# base.net
KiCad netlist of a schematic drawn in EAGLE
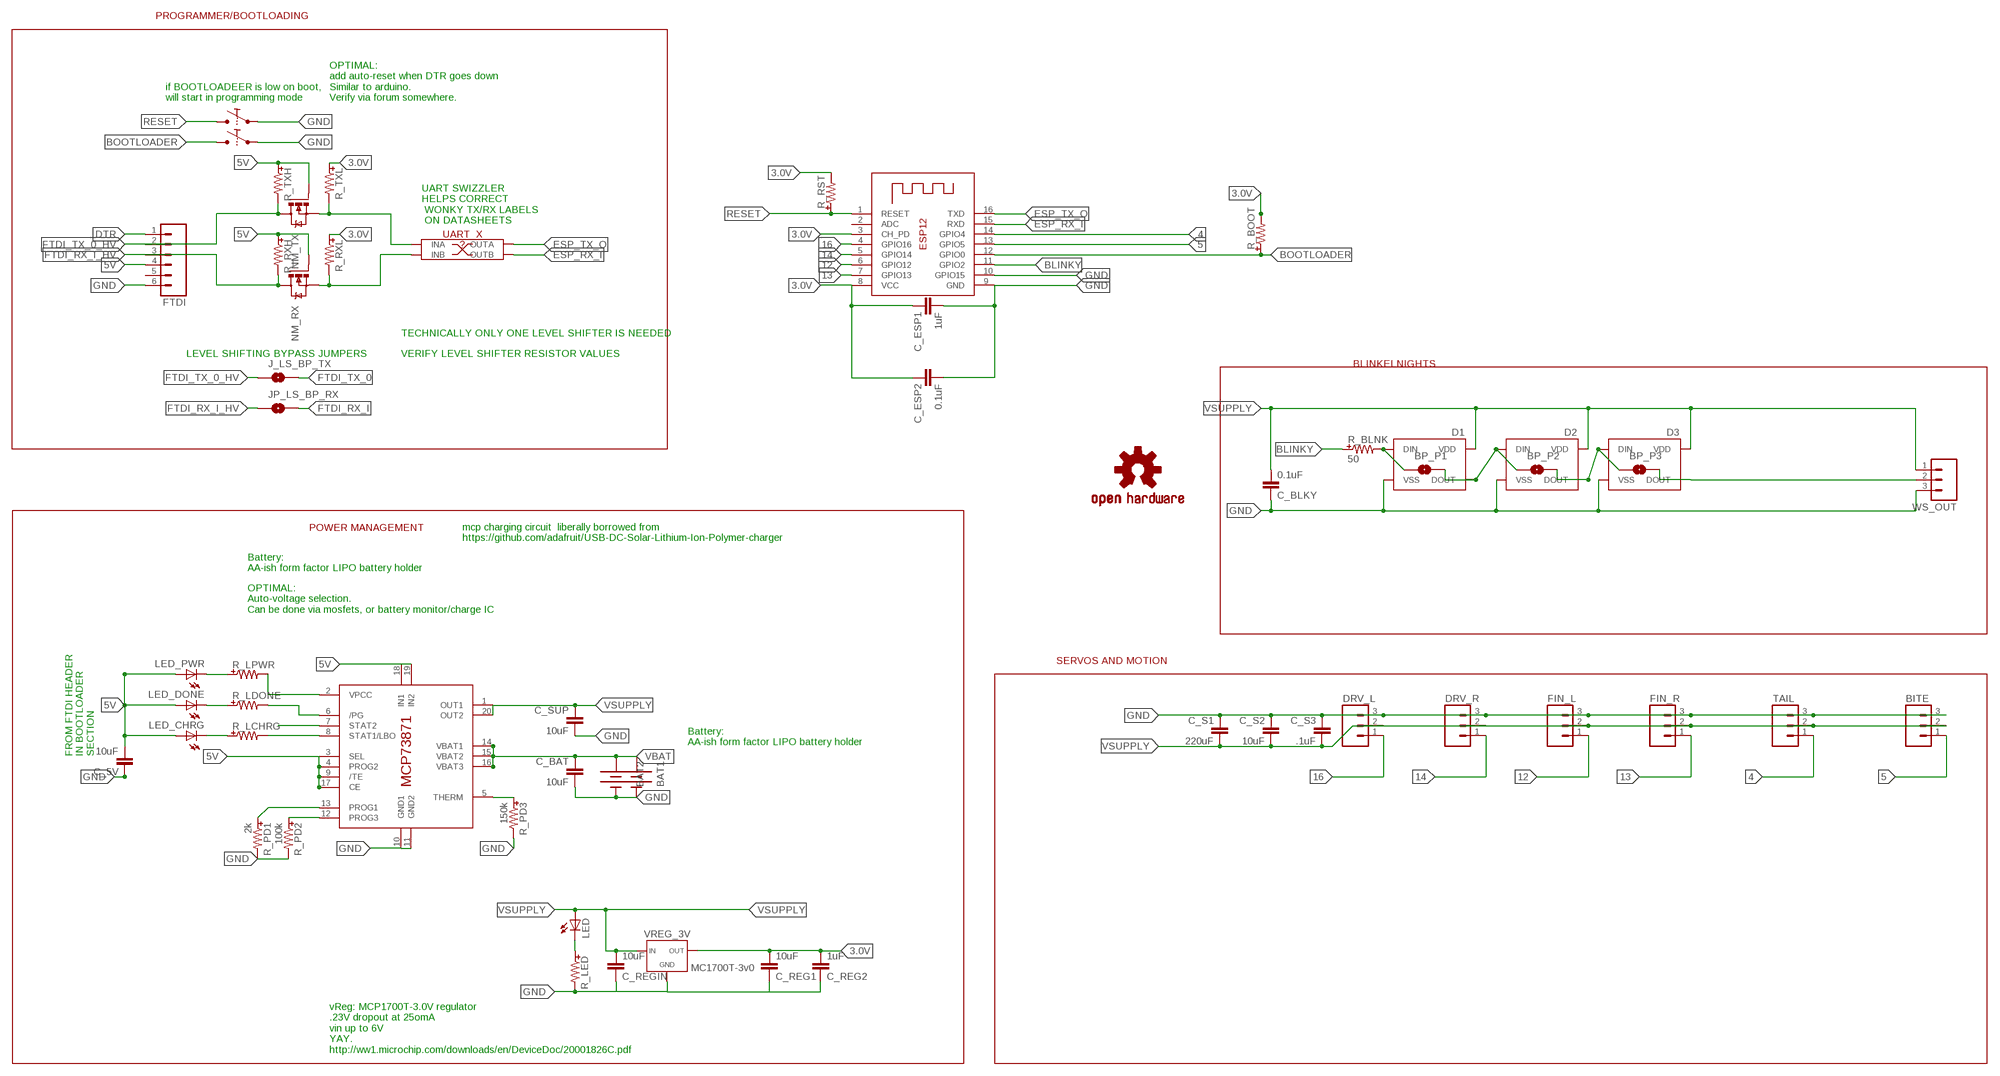
[diagram p0: schematic, sheet 1]

(export (version "E")
  (design (tool "Eeschema 10.0.6"))
  (components
    (comp (ref "BAT1")
      (value "BATTERY18650")
      (footprint "eagle-import:BATTERY_18650-HOLDER")
      (libsource (lib "eagle-import") (part "BATTERY18650"))
    )
    (comp (ref "BAT2")
      (value "BATTERYAA")
      (footprint "eagle-import:BATTERY-AA")
      (libsource (lib "eagle-import") (part "BATTERYAA"))
    )
    (comp (ref "BITE")
      (value "M03LOCK")
      (footprint "eagle-import:1X03_LOCK")
      (libsource (lib "eagle-import") (part "M03LOCK"))
    )
    (comp (ref "BP_P1")
      (value "JUMPER-PAD-2-NOYES_SILK")
      (footprint "eagle-import:PAD-JUMPER-2-NO_YES_SILK")
      (libsource (lib "eagle-import") (part "JUMPER-PAD-2-NOYES_SILK"))
    )
    (comp (ref "BP_P2")
      (value "JUMPER-PAD-2-NOYES_SILK")
      (footprint "eagle-import:PAD-JUMPER-2-NO_YES_SILK")
      (libsource (lib "eagle-import") (part "JUMPER-PAD-2-NOYES_SILK"))
    )
    (comp (ref "BP_P3")
      (value "JUMPER-PAD-2-NOYES_SILK")
      (footprint "eagle-import:PAD-JUMPER-2-NO_YES_SILK")
      (libsource (lib "eagle-import") (part "JUMPER-PAD-2-NOYES_SILK"))
    )
    (comp (ref "BTN_PROG")
      (value "BUTTONPJRC")
      (footprint "eagle-import:BUTTON-PJRC")
      (libsource (lib "eagle-import") (part "BUTTONPJRC"))
    )
    (comp (ref "BTN_RST")
      (value "BUTTONPJRC")
      (footprint "eagle-import:BUTTON-PJRC")
      (libsource (lib "eagle-import") (part "BUTTONPJRC"))
    )
    (comp (ref "C_5V")
      (value "10uF")
      (footprint "eagle-import:0402-0603-0805-UNIVERSAL")
      (libsource (lib "eagle-import") (part "CAPUNIVERSAL"))
    )
    (comp (ref "C_BAT")
      (value "10uF")
      (footprint "eagle-import:0402-0603-0805-UNIVERSAL")
      (libsource (lib "eagle-import") (part "CAPUNIVERSAL"))
    )
    (comp (ref "C_BLKY")
      (value "0.1uF")
      (footprint "eagle-import:0402-0603-0805-UNIVERSAL")
      (libsource (lib "eagle-import") (part "CAPUNIVERSAL"))
    )
    (comp (ref "C_ESP1")
      (value "1uF")
      (footprint "eagle-import:0402-0603-0805-UNIVERSAL")
      (libsource (lib "eagle-import") (part "CAPUNIVERSAL"))
    )
    (comp (ref "C_ESP2")
      (value "0.1uF")
      (footprint "eagle-import:0402-0603-0805-UNIVERSAL")
      (libsource (lib "eagle-import") (part "CAPUNIVERSAL"))
    )
    (comp (ref "C_REG1")
      (value "10uF")
      (footprint "eagle-import:0402-0603-0805-UNIVERSAL")
      (libsource (lib "eagle-import") (part "CAPUNIVERSAL"))
    )
    (comp (ref "C_REG2")
      (value "1uF")
      (footprint "eagle-import:0402-0603-0805-UNIVERSAL")
      (libsource (lib "eagle-import") (part "CAPUNIVERSAL"))
    )
    (comp (ref "C_REGIN")
      (value "10uF")
      (footprint "eagle-import:0402-0603-0805-UNIVERSAL")
      (libsource (lib "eagle-import") (part "CAPUNIVERSAL"))
    )
    (comp (ref "C_S1")
      (value "220uF")
      (footprint "eagle-import:0402-0603-0805-UNIVERSAL")
      (libsource (lib "eagle-import") (part "CAPUNIVERSAL"))
    )
    (comp (ref "C_S2")
      (value "10uF")
      (footprint "eagle-import:0402-0603-0805-UNIVERSAL")
      (libsource (lib "eagle-import") (part "CAPUNIVERSAL"))
    )
    (comp (ref "C_S3")
      (value ".1uF")
      (footprint "eagle-import:0402-0603-0805-UNIVERSAL")
      (libsource (lib "eagle-import") (part "CAPUNIVERSAL"))
    )
    (comp (ref "C_SUP")
      (value "10uF")
      (footprint "eagle-import:0402-0603-0805-UNIVERSAL")
      (libsource (lib "eagle-import") (part "CAPUNIVERSAL"))
    )
    (comp (ref "D1")
      (value "WS2812B")
      (footprint "eagle-import:WS2812B")
      (libsource (lib "eagle-import") (part "WS2812B"))
    )
    (comp (ref "D2")
      (value "WS2812B")
      (footprint "eagle-import:WS2812B")
      (libsource (lib "eagle-import") (part "WS2812B"))
    )
    (comp (ref "D3")
      (value "WS2812B")
      (footprint "eagle-import:WS2812B")
      (libsource (lib "eagle-import") (part "WS2812B"))
    )
    (comp (ref "DRV_L")
      (value "M03LOCK")
      (footprint "eagle-import:1X03_LOCK")
      (libsource (lib "eagle-import") (part "M03LOCK"))
    )
    (comp (ref "DRV_R")
      (value "M03LOCK")
      (footprint "eagle-import:1X03_LOCK")
      (libsource (lib "eagle-import") (part "M03LOCK"))
    )
    (comp (ref "FIN_L")
      (value "M03LOCK")
      (footprint "eagle-import:1X03_LOCK")
      (libsource (lib "eagle-import") (part "M03LOCK"))
    )
    (comp (ref "FIN_R")
      (value "M03LOCK")
      (footprint "eagle-import:1X03_LOCK")
      (libsource (lib "eagle-import") (part "M03LOCK"))
    )
    (comp (ref "FTDI")
      (value "M06LOCK")
      (footprint "eagle-import:1X06_LOCK")
      (libsource (lib "eagle-import") (part "M06LOCK"))
    )
    (comp (ref "IC_LIPO")
      (value "MCP73871")
      (footprint "eagle-import:QFN20")
      (libsource (lib "eagle-import") (part "MCP73871"))
    )
    (comp (ref "JP_LS_BP_RX")
      (value "JUMPER-PAD-2-NOYES_SILK")
      (footprint "eagle-import:PAD-JUMPER-2-NO_YES_SILK")
      (libsource (lib "eagle-import") (part "JUMPER-PAD-2-NOYES_SILK"))
    )
    (comp (ref "J_LS_BP_TX")
      (value "JUMPER-PAD-2-NOYES_SILK")
      (footprint "eagle-import:PAD-JUMPER-2-NO_YES_SILK")
      (libsource (lib "eagle-import") (part "JUMPER-PAD-2-NOYES_SILK"))
    )
    (comp (ref "LED")
      (value "LEDUNIVERSAL")
      (footprint "eagle-import:0402-0603-0805-UNIVERSAL")
      (libsource (lib "eagle-import") (part "LEDUNIVERSAL"))
    )
    (comp (ref "LED_CHRG")
      (value "LEDUNIVERSAL")
      (footprint "eagle-import:0402-0603-0805-UNIVERSAL")
      (libsource (lib "eagle-import") (part "LEDUNIVERSAL"))
    )
    (comp (ref "LED_DONE")
      (value "LEDUNIVERSAL")
      (footprint "eagle-import:0402-0603-0805-UNIVERSAL")
      (libsource (lib "eagle-import") (part "LEDUNIVERSAL"))
    )
    (comp (ref "LED_PWR")
      (value "LEDUNIVERSAL")
      (footprint "eagle-import:0402-0603-0805-UNIVERSAL")
      (libsource (lib "eagle-import") (part "LEDUNIVERSAL"))
    )
    (comp (ref "LOGO1")
      (value "OSHW-LOGOS")
      (footprint "eagle-import:OSHW-LOGO-S")
      (libsource (lib "eagle-import") (part "OSHW-LOGOS"))
    )
    (comp (ref "NM_RX")
      (value "MOSFET-NCHANNELSMD")
      (footprint "eagle-import:SOT23-3")
      (libsource (lib "eagle-import") (part "MOSFET-NCHANNELSMD"))
    )
    (comp (ref "NM_TX")
      (value "MOSFET-NCHANNELSMD")
      (footprint "eagle-import:SOT23-3")
      (libsource (lib "eagle-import") (part "MOSFET-NCHANNELSMD"))
    )
    (comp (ref "R_BLNK")
      (value "50")
      (footprint "eagle-import:0402-0603-0805-UNIVERSAL")
      (libsource (lib "eagle-import") (part "RESISTORUNIVERSAL"))
    )
    (comp (ref "R_BOOT")
      (value "RESISTORUNIVERSAL")
      (footprint "eagle-import:0402-0603-0805-UNIVERSAL")
      (libsource (lib "eagle-import") (part "RESISTORUNIVERSAL"))
    )
    (comp (ref "R_LCHRG")
      (value "RESISTORUNIVERSAL")
      (footprint "eagle-import:0402-0603-0805-UNIVERSAL")
      (libsource (lib "eagle-import") (part "RESISTORUNIVERSAL"))
    )
    (comp (ref "R_LDONE")
      (value "RESISTORUNIVERSAL")
      (footprint "eagle-import:0402-0603-0805-UNIVERSAL")
      (libsource (lib "eagle-import") (part "RESISTORUNIVERSAL"))
    )
    (comp (ref "R_LED")
      (value "RESISTORUNIVERSAL")
      (footprint "eagle-import:0402-0603-0805-UNIVERSAL")
      (libsource (lib "eagle-import") (part "RESISTORUNIVERSAL"))
    )
    (comp (ref "R_LPWR")
      (value "RESISTORUNIVERSAL")
      (footprint "eagle-import:0402-0603-0805-UNIVERSAL")
      (libsource (lib "eagle-import") (part "RESISTORUNIVERSAL"))
    )
    (comp (ref "R_PD1")
      (value "2k")
      (footprint "eagle-import:0402-0603-0805-UNIVERSAL")
      (libsource (lib "eagle-import") (part "RESISTORUNIVERSAL"))
    )
    (comp (ref "R_PD2")
      (value "100k")
      (footprint "eagle-import:0402-0603-0805-UNIVERSAL")
      (libsource (lib "eagle-import") (part "RESISTORUNIVERSAL"))
    )
    (comp (ref "R_PD3")
      (value "150k")
      (footprint "eagle-import:0402-0603-0805-UNIVERSAL")
      (libsource (lib "eagle-import") (part "RESISTORUNIVERSAL"))
    )
    (comp (ref "R_RST")
      (value "RESISTORUNIVERSAL")
      (footprint "eagle-import:0402-0603-0805-UNIVERSAL")
      (libsource (lib "eagle-import") (part "RESISTORUNIVERSAL"))
    )
    (comp (ref "R_RXH")
      (value "RESISTORUNIVERSAL")
      (footprint "eagle-import:0402-0603-0805-UNIVERSAL")
      (libsource (lib "eagle-import") (part "RESISTORUNIVERSAL"))
    )
    (comp (ref "R_RXL")
      (value "RESISTORUNIVERSAL")
      (footprint "eagle-import:0402-0603-0805-UNIVERSAL")
      (libsource (lib "eagle-import") (part "RESISTORUNIVERSAL"))
    )
    (comp (ref "R_TXH")
      (value "RESISTORUNIVERSAL")
      (footprint "eagle-import:0402-0603-0805-UNIVERSAL")
      (libsource (lib "eagle-import") (part "RESISTORUNIVERSAL"))
    )
    (comp (ref "R_TXL")
      (value "RESISTORUNIVERSAL")
      (footprint "eagle-import:0402-0603-0805-UNIVERSAL")
      (libsource (lib "eagle-import") (part "RESISTORUNIVERSAL"))
    )
    (comp (ref "TAIL")
      (value "M03LOCK")
      (footprint "eagle-import:1X03_LOCK")
      (libsource (lib "eagle-import") (part "M03LOCK"))
    )
    (comp (ref "UART_X")
      (value "UART_SWITCHER0603")
      (footprint "eagle-import:UART_SWITCHER_0603")
      (libsource (lib "eagle-import") (part "UART_SWITCHER0603"))
    )
    (comp (ref "VREG_3V")
      (value "MC1700T-3v0")
      (footprint "eagle-import:SOT23")
      (libsource (lib "eagle-import") (part "VOLTAGE-REGULATORMCP1703"))
    )
    (comp (ref "WS_OUT")
      (value "M03LOCK")
      (footprint "eagle-import:1X03_LOCK")
      (libsource (lib "eagle-import") (part "M03LOCK"))
    )
    (comp (ref "X1")
      (value "ESP-12")
      (footprint "eagle-import:ESP-12")
      (libsource (lib "eagle-import") (part "ESP-12"))
    )
  )
  (nets
    (net (code "1") (name "3.0V") (class "Default")
      (node (ref "C_ESP1") (pin "-") (pinfunction "1_-") (pintype "passive"))
      (node (ref "C_ESP2") (pin "-") (pinfunction "1_-") (pintype "passive"))
      (node (ref "C_REG1") (pin "+") (pinfunction "2_+") (pintype "passive"))
      (node (ref "C_REG2") (pin "+") (pinfunction "2_+") (pintype "passive"))
      (node (ref "R_BOOT") (pin "-") (pinfunction "2_-") (pintype "passive"))
      (node (ref "R_RST") (pin "-") (pinfunction "2_-") (pintype "passive"))
      (node (ref "R_RXL") (pin "+") (pinfunction "1_+") (pintype "passive"))
      (node (ref "R_TXL") (pin "+") (pinfunction "1_+") (pintype "passive"))
      (node (ref "VREG_3V") (pin "2") (pinfunction "OUT_2") (pintype "input"))
      (node (ref "X1") (pin "3") (pinfunction "CH_PD_3") (pintype "input"))
      (node (ref "X1") (pin "8") (pinfunction "VCC_8") (pintype "power_in"))
    )
    (net (code "2") (name "4") (class "Default")
      (node (ref "TAIL") (pin "1") (pinfunction "1_1") (pintype "passive"))
      (node (ref "X1") (pin "14") (pinfunction "GPIO4_14") (pintype "bidirectional"))
    )
    (net (code "3") (name "5") (class "Default")
      (node (ref "BITE") (pin "1") (pinfunction "1_1") (pintype "passive"))
      (node (ref "X1") (pin "13") (pinfunction "GPIO5_13") (pintype "bidirectional"))
    )
    (net (code "4") (name "5V") (class "Default")
      (node (ref "C_5V") (pin "+") (pinfunction "2_+") (pintype "passive"))
      (node (ref "FTDI") (pin "4") (pinfunction "4_4") (pintype "passive"))
      (node (ref "IC_LIPO") (pin "17") (pinfunction "CE_17") (pintype "input"))
      (node (ref "IC_LIPO") (pin "18") (pinfunction "IN1_18") (pintype "input"))
      (node (ref "IC_LIPO") (pin "19") (pinfunction "IN2_19") (pintype "input"))
      (node (ref "IC_LIPO") (pin "3") (pinfunction "SEL_3") (pintype "input"))
      (node (ref "IC_LIPO") (pin "4") (pinfunction "PROG2_4") (pintype "input"))
      (node (ref "IC_LIPO") (pin "9") (pinfunction "/TE_9") (pintype "input"))
      (node (ref "LED_CHRG") (pin "+") (pinfunction "A_+") (pintype "passive"))
      (node (ref "LED_DONE") (pin "+") (pinfunction "A_+") (pintype "passive"))
      (node (ref "LED_PWR") (pin "+") (pinfunction "A_+") (pintype "passive"))
      (node (ref "NM_RX") (pin "1") (pinfunction "G_1") (pintype "passive"))
      (node (ref "NM_TX") (pin "1") (pinfunction "G_1") (pintype "passive"))
      (node (ref "R_RXH") (pin "+") (pinfunction "1_+") (pintype "passive"))
      (node (ref "R_TXH") (pin "+") (pinfunction "1_+") (pintype "passive"))
    )
    (net (code "5") (name "12") (class "Default")
      (node (ref "FIN_L") (pin "1") (pinfunction "1_1") (pintype "passive"))
      (node (ref "X1") (pin "6") (pinfunction "GPIO12_6") (pintype "bidirectional"))
    )
    (net (code "6") (name "13") (class "Default")
      (node (ref "FIN_R") (pin "1") (pinfunction "1_1") (pintype "passive"))
      (node (ref "X1") (pin "7") (pinfunction "GPIO13_7") (pintype "bidirectional"))
    )
    (net (code "7") (name "14") (class "Default")
      (node (ref "DRV_R") (pin "1") (pinfunction "1_1") (pintype "passive"))
      (node (ref "X1") (pin "5") (pinfunction "GPIO14_5") (pintype "bidirectional"))
    )
    (net (code "8") (name "16") (class "Default")
      (node (ref "DRV_L") (pin "1") (pinfunction "1_1") (pintype "passive"))
      (node (ref "X1") (pin "4") (pinfunction "GPIO16_4") (pintype "bidirectional"))
    )
    (net (code "9") (name "BLINKY") (class "Default")
      (node (ref "R_BLNK") (pin "+") (pinfunction "1_+") (pintype "passive"))
      (node (ref "X1") (pin "11") (pinfunction "GPIO2_11") (pintype "bidirectional"))
    )
    (net (code "10") (name "BOOTLOADER") (class "Default")
      (node (ref "BTN_PROG") (pin "A1") (pinfunction "P$1_A1") (pintype "bidirectional"))
      (node (ref "BTN_PROG") (pin "A2") (pinfunction "P$1_A2") (pintype "bidirectional"))
      (node (ref "R_BOOT") (pin "+") (pinfunction "1_+") (pintype "passive"))
      (node (ref "X1") (pin "12") (pinfunction "GPIO0_12") (pintype "bidirectional"))
    )
    (net (code "11") (name "DTR") (class "Default")
      (node (ref "FTDI") (pin "1") (pinfunction "1_1") (pintype "passive"))
    )
    (net (code "12") (name "ESP_RX_I") (class "Default")
      (node (ref "UART_X") (pin "TX_B") (pinfunction "OUTB_TX_B") (pintype "bidirectional"))
      (node (ref "X1") (pin "15") (pinfunction "RXD_15") (pintype "input"))
    )
    (net (code "13") (name "ESP_TX_O") (class "Default")
      (node (ref "UART_X") (pin "RX_B") (pinfunction "OUTA_RX_B") (pintype "bidirectional"))
      (node (ref "X1") (pin "16") (pinfunction "TXD_16") (pintype "output"))
    )
    (net (code "14") (name "FTDI_RX_I") (class "Default")
      (node (ref "JP_LS_BP_RX") (pin "2") (pinfunction "2_2") (pintype "passive"))
      (node (ref "NM_RX") (pin "2") (pinfunction "S_2") (pintype "passive"))
      (node (ref "R_RXL") (pin "-") (pinfunction "2_-") (pintype "passive"))
      (node (ref "UART_X") (pin "RX_A") (pinfunction "INB_RX_A") (pintype "bidirectional"))
    )
    (net (code "15") (name "FTDI_RX_I_HV") (class "Default")
      (node (ref "FTDI") (pin "3") (pinfunction "3_3") (pintype "passive"))
      (node (ref "JP_LS_BP_RX") (pin "1") (pinfunction "1_1") (pintype "passive"))
      (node (ref "NM_RX") (pin "3") (pinfunction "D_3") (pintype "passive"))
      (node (ref "R_RXH") (pin "-") (pinfunction "2_-") (pintype "passive"))
    )
    (net (code "16") (name "FTDI_TX_0") (class "Default")
      (node (ref "J_LS_BP_TX") (pin "2") (pinfunction "2_2") (pintype "passive"))
      (node (ref "NM_TX") (pin "2") (pinfunction "S_2") (pintype "passive"))
      (node (ref "R_TXL") (pin "-") (pinfunction "2_-") (pintype "passive"))
      (node (ref "UART_X") (pin "TX_A") (pinfunction "INA_TX_A") (pintype "bidirectional"))
    )
    (net (code "17") (name "FTDI_TX_0_HV") (class "Default")
      (node (ref "FTDI") (pin "2") (pinfunction "2_2") (pintype "passive"))
      (node (ref "J_LS_BP_TX") (pin "1") (pinfunction "1_1") (pintype "passive"))
      (node (ref "NM_TX") (pin "3") (pinfunction "D_3") (pintype "passive"))
      (node (ref "R_TXH") (pin "-") (pinfunction "2_-") (pintype "passive"))
    )
    (net (code "18") (name "GND") (class "Default")
      (node (ref "BAT1") (pin "GND@1") (pinfunction "-_GND@1") (pintype "power_in"))
      (node (ref "BAT2") (pin "GND@1") (pinfunction "-_GND@1") (pintype "power_in"))
      (node (ref "BITE") (pin "3") (pinfunction "3_3") (pintype "passive"))
      (node (ref "BTN_PROG") (pin "B1") (pinfunction "P$2_B1") (pintype "bidirectional"))
      (node (ref "BTN_PROG") (pin "B2") (pinfunction "P$2_B2") (pintype "bidirectional"))
      (node (ref "BTN_RST") (pin "B1") (pinfunction "P$2_B1") (pintype "bidirectional"))
      (node (ref "BTN_RST") (pin "B2") (pinfunction "P$2_B2") (pintype "bidirectional"))
      (node (ref "C_5V") (pin "-") (pinfunction "1_-") (pintype "passive"))
      (node (ref "C_BAT") (pin "+") (pinfunction "2_+") (pintype "passive"))
      (node (ref "C_BLKY") (pin "-") (pinfunction "1_-") (pintype "passive"))
      (node (ref "C_ESP1") (pin "+") (pinfunction "2_+") (pintype "passive"))
      (node (ref "C_ESP2") (pin "+") (pinfunction "2_+") (pintype "passive"))
      (node (ref "C_REG1") (pin "-") (pinfunction "1_-") (pintype "passive"))
      (node (ref "C_REG2") (pin "-") (pinfunction "1_-") (pintype "passive"))
      (node (ref "C_REGIN") (pin "-") (pinfunction "1_-") (pintype "passive"))
      (node (ref "C_S1") (pin "-") (pinfunction "1_-") (pintype "passive"))
      (node (ref "C_S2") (pin "-") (pinfunction "1_-") (pintype "passive"))
      (node (ref "C_S3") (pin "-") (pinfunction "1_-") (pintype "passive"))
      (node (ref "C_SUP") (pin "+") (pinfunction "2_+") (pintype "passive"))
      (node (ref "D1") (pin "3") (pinfunction "VSS_3") (pintype "power_in"))
      (node (ref "D2") (pin "3") (pinfunction "VSS_3") (pintype "power_in"))
      (node (ref "D3") (pin "3") (pinfunction "VSS_3") (pintype "power_in"))
      (node (ref "DRV_L") (pin "3") (pinfunction "3_3") (pintype "passive"))
      (node (ref "DRV_R") (pin "3") (pinfunction "3_3") (pintype "passive"))
      (node (ref "FIN_L") (pin "3") (pinfunction "3_3") (pintype "passive"))
      (node (ref "FIN_R") (pin "3") (pinfunction "3_3") (pintype "passive"))
      (node (ref "FTDI") (pin "6") (pinfunction "6_6") (pintype "passive"))
      (node (ref "IC_LIPO") (pin "10") (pinfunction "GND1_10") (pintype "power_in"))
      (node (ref "IC_LIPO") (pin "11") (pinfunction "GND2_11") (pintype "power_in"))
      (node (ref "R_LED") (pin "-") (pinfunction "2_-") (pintype "passive"))
      (node (ref "R_PD1") (pin "-") (pinfunction "2_-") (pintype "passive"))
      (node (ref "R_PD2") (pin "-") (pinfunction "2_-") (pintype "passive"))
      (node (ref "R_PD3") (pin "-") (pinfunction "2_-") (pintype "passive"))
      (node (ref "TAIL") (pin "3") (pinfunction "3_3") (pintype "passive"))
      (node (ref "VREG_3V") (pin "1") (pinfunction "GND_1") (pintype "input"))
      (node (ref "WS_OUT") (pin "3") (pinfunction "3_3") (pintype "passive"))
      (node (ref "X1") (pin "10") (pinfunction "GPIO15_10") (pintype "bidirectional"))
      (node (ref "X1") (pin "9") (pinfunction "GND_9") (pintype "power_in"))
    )
    (net (code "19") (name "Net-(D1-DIN)") (class "Default")
      (node (ref "BP_P1") (pin "1") (pinfunction "1_1") (pintype "passive"))
      (node (ref "D1") (pin "4") (pinfunction "DIN_4") (pintype "input"))
      (node (ref "R_BLNK") (pin "-") (pinfunction "2_-") (pintype "passive"))
    )
    (net (code "20") (name "Net-(D1-DOUT)") (class "Default")
      (node (ref "BP_P1") (pin "2") (pinfunction "2_2") (pintype "passive"))
      (node (ref "BP_P2") (pin "1") (pinfunction "1_1") (pintype "passive"))
      (node (ref "D1") (pin "2") (pinfunction "DOUT_2") (pintype "output"))
      (node (ref "D2") (pin "4") (pinfunction "DIN_4") (pintype "input"))
    )
    (net (code "21") (name "Net-(D2-DOUT)") (class "Default")
      (node (ref "BP_P2") (pin "2") (pinfunction "2_2") (pintype "passive"))
      (node (ref "BP_P3") (pin "1") (pinfunction "1_1") (pintype "passive"))
      (node (ref "D2") (pin "2") (pinfunction "DOUT_2") (pintype "output"))
      (node (ref "D3") (pin "4") (pinfunction "DIN_4") (pintype "input"))
    )
    (net (code "22") (name "Net-(D3-DOUT)") (class "Default")
      (node (ref "BP_P3") (pin "2") (pinfunction "2_2") (pintype "passive"))
      (node (ref "D3") (pin "2") (pinfunction "DOUT_2") (pintype "output"))
      (node (ref "WS_OUT") (pin "2") (pinfunction "2_2") (pintype "passive"))
    )
    (net (code "23") (name "Net-(IC_LIPO-PROG1)") (class "Default")
      (node (ref "IC_LIPO") (pin "13") (pinfunction "PROG1_13") (pintype "input"))
      (node (ref "R_PD1") (pin "+") (pinfunction "1_+") (pintype "passive"))
    )
    (net (code "24") (name "Net-(IC_LIPO-PROG3)") (class "Default")
      (node (ref "IC_LIPO") (pin "12") (pinfunction "PROG3_12") (pintype "input"))
      (node (ref "R_PD2") (pin "+") (pinfunction "1_+") (pintype "passive"))
    )
    (net (code "25") (name "Net-(IC_LIPO-STAT1{slash}LBO)") (class "Default")
      (node (ref "IC_LIPO") (pin "8") (pinfunction "STAT1/LBO_8") (pintype "output"))
      (node (ref "R_LCHRG") (pin "-") (pinfunction "2_-") (pintype "passive"))
    )
    (net (code "26") (name "Net-(IC_LIPO-THERM)") (class "Default")
      (node (ref "IC_LIPO") (pin "5") (pinfunction "THERM_5") (pintype "input"))
      (node (ref "R_PD3") (pin "+") (pinfunction "1_+") (pintype "passive"))
    )
    (net (code "27") (name "Net-(IC_LIPO-VPCC)") (class "Default")
      (node (ref "IC_LIPO") (pin "2") (pinfunction "VPCC_2") (pintype "input"))
      (node (ref "R_LPWR") (pin "-") (pinfunction "2_-") (pintype "passive"))
    )
    (net (code "28") (name "Net-(IC_LIPO-{slash}PG)") (class "Default")
      (node (ref "IC_LIPO") (pin "6") (pinfunction "/PG_6") (pintype "output"))
      (node (ref "R_LDONE") (pin "-") (pinfunction "2_-") (pintype "passive"))
    )
    (net (code "29") (name "Net-(LED-C)") (class "Default")
      (node (ref "LED") (pin "-") (pinfunction "C_-") (pintype "passive"))
      (node (ref "R_LED") (pin "+") (pinfunction "1_+") (pintype "passive"))
    )
    (net (code "30") (name "Net-(LED_CHRG-C)") (class "Default")
      (node (ref "LED_CHRG") (pin "-") (pinfunction "C_-") (pintype "passive"))
      (node (ref "R_LCHRG") (pin "+") (pinfunction "1_+") (pintype "passive"))
    )
    (net (code "31") (name "Net-(LED_DONE-C)") (class "Default")
      (node (ref "LED_DONE") (pin "-") (pinfunction "C_-") (pintype "passive"))
      (node (ref "R_LDONE") (pin "+") (pinfunction "1_+") (pintype "passive"))
    )
    (net (code "32") (name "Net-(LED_PWR-C)") (class "Default")
      (node (ref "LED_PWR") (pin "-") (pinfunction "C_-") (pintype "passive"))
      (node (ref "R_LPWR") (pin "+") (pinfunction "1_+") (pintype "passive"))
    )
    (net (code "33") (name "RESET") (class "Default")
      (node (ref "BTN_RST") (pin "A1") (pinfunction "P$1_A1") (pintype "bidirectional"))
      (node (ref "BTN_RST") (pin "A2") (pinfunction "P$1_A2") (pintype "bidirectional"))
      (node (ref "R_RST") (pin "+") (pinfunction "1_+") (pintype "passive"))
      (node (ref "X1") (pin "1") (pinfunction "RESET_1") (pintype "input"))
    )
    (net (code "34") (name "VBAT") (class "Default")
      (node (ref "BAT1") (pin "PWR@1") (pinfunction "+_PWR@1") (pintype "power_in"))
      (node (ref "BAT2") (pin "PWR@1") (pinfunction "+_PWR@1") (pintype "power_in"))
      (node (ref "C_BAT") (pin "-") (pinfunction "1_-") (pintype "passive"))
      (node (ref "IC_LIPO") (pin "14") (pinfunction "VBAT1_14") (pintype "output"))
      (node (ref "IC_LIPO") (pin "15") (pinfunction "VBAT2_15") (pintype "output"))
      (node (ref "IC_LIPO") (pin "16") (pinfunction "VBAT3_16") (pintype "output"))
    )
    (net (code "35") (name "VSUPPLY") (class "Default")
      (node (ref "BITE") (pin "2") (pinfunction "2_2") (pintype "passive"))
      (node (ref "C_BLKY") (pin "+") (pinfunction "2_+") (pintype "passive"))
      (node (ref "C_REGIN") (pin "+") (pinfunction "2_+") (pintype "passive"))
      (node (ref "C_S1") (pin "+") (pinfunction "2_+") (pintype "passive"))
      (node (ref "C_S2") (pin "+") (pinfunction "2_+") (pintype "passive"))
      (node (ref "C_S3") (pin "+") (pinfunction "2_+") (pintype "passive"))
      (node (ref "C_SUP") (pin "-") (pinfunction "1_-") (pintype "passive"))
      (node (ref "D1") (pin "1") (pinfunction "VDD_1") (pintype "power_in"))
      (node (ref "D2") (pin "1") (pinfunction "VDD_1") (pintype "power_in"))
      (node (ref "D3") (pin "1") (pinfunction "VDD_1") (pintype "power_in"))
      (node (ref "DRV_L") (pin "2") (pinfunction "2_2") (pintype "passive"))
      (node (ref "DRV_R") (pin "2") (pinfunction "2_2") (pintype "passive"))
      (node (ref "FIN_L") (pin "2") (pinfunction "2_2") (pintype "passive"))
      (node (ref "FIN_R") (pin "2") (pinfunction "2_2") (pintype "passive"))
      (node (ref "IC_LIPO") (pin "1") (pinfunction "OUT1_1") (pintype "output"))
      (node (ref "IC_LIPO") (pin "20") (pinfunction "OUT2_20") (pintype "output"))
      (node (ref "LED") (pin "+") (pinfunction "A_+") (pintype "passive"))
      (node (ref "TAIL") (pin "2") (pinfunction "2_2") (pintype "passive"))
      (node (ref "VREG_3V") (pin "3") (pinfunction "IN_3") (pintype "input"))
      (node (ref "WS_OUT") (pin "1") (pinfunction "1_1") (pintype "passive"))
    )
    (net (code "36") (name "unconnected-(FTDI-Pad5)") (class "Default")
      (node (ref "FTDI") (pin "5") (pinfunction "5_5") (pintype "passive"))
    )
    (net (code "37") (name "unconnected-(IC_LIPO-STAT2-Pad7)") (class "Default")
      (node (ref "IC_LIPO") (pin "7") (pinfunction "STAT2_7") (pintype "output"))
    )
    (net (code "38") (name "unconnected-(X1-ADC-Pad2)") (class "Default")
      (node (ref "X1") (pin "2") (pinfunction "ADC_2") (pintype "passive"))
    )
  )
)
